# Input_Conditioner.net
KiCad netlist of a schematic drawn in Altium Designer
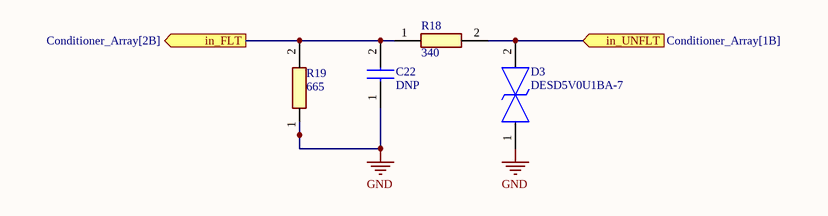
[diagram p0: Input_Conditioner.SchDoc]

(export (version "E")
  (design (tool "Eeschema 10.0.6"))
  (components
    (comp (ref "C22")
      (value "DNP")
      (footprint "SamacSys:CAPC1608X90N")
      (description "CL10B225KP8NNNC")
      (fields (field (name "MOUSER PART NUMBER") "187-CL10B225KP8NNNC"))
      (libsource (lib "*") (part "CL10B225KP8NNNC"))
    )
    (comp (ref "D3")
      (value "DESD5V0U1BA-7")
      (footprint "SamacSys:SOD2513X120N")
      (description "TVS Diode (Bi-directional)")
      (fields (field (name "MOUSER PART NUMBER") "621-DESD5V0U1BA-7"))
      (libsource (lib "*") (part "DESD5V0U1BA-7"))
    )
    (comp (ref "R18")
      (value "340")
      (footprint "SamacSys:RESC1608X55N")
      (description "RC0603FR-07340RL")
      (libsource (lib "*") (part "RC0603FR-07340RL"))
    )
    (comp (ref "R19")
      (value "665")
      (footprint "SamacSys:RESC1608X55N")
      (description "RC0603FR-07665RL")
      (fields (field (name "MOUSER PART NUMBER") "603-RC0603FR-07665RL"))
      (libsource (lib "*") (part "RC0603FR-07665RL"))
    )
  )
  (nets
    (net (code "1") (name "/in_FLT") (class "Default")
      (node (ref "C22") (pin "2") (pinfunction "2_2") (pintype "passive"))
      (node (ref "R18") (pin "1") (pinfunction "1_1") (pintype "passive"))
      (node (ref "R19") (pin "2") (pinfunction "2_2") (pintype "passive"))
    )
    (net (code "2") (name "/in_UNFLT") (class "Default")
      (node (ref "D3") (pin "2") (pinfunction "2_2") (pintype "passive"))
      (node (ref "R18") (pin "2") (pinfunction "2_2") (pintype "passive"))
    )
    (net (code "3") (name "GND") (class "Default")
      (node (ref "C22") (pin "1") (pinfunction "1_1") (pintype "passive"))
      (node (ref "D3") (pin "1") (pinfunction "1_1") (pintype "passive"))
      (node (ref "R19") (pin "1") (pinfunction "1_1") (pintype "passive"))
    )
  )
)
